# Training_Board.net
KiCad netlist of a schematic drawn in EAGLE
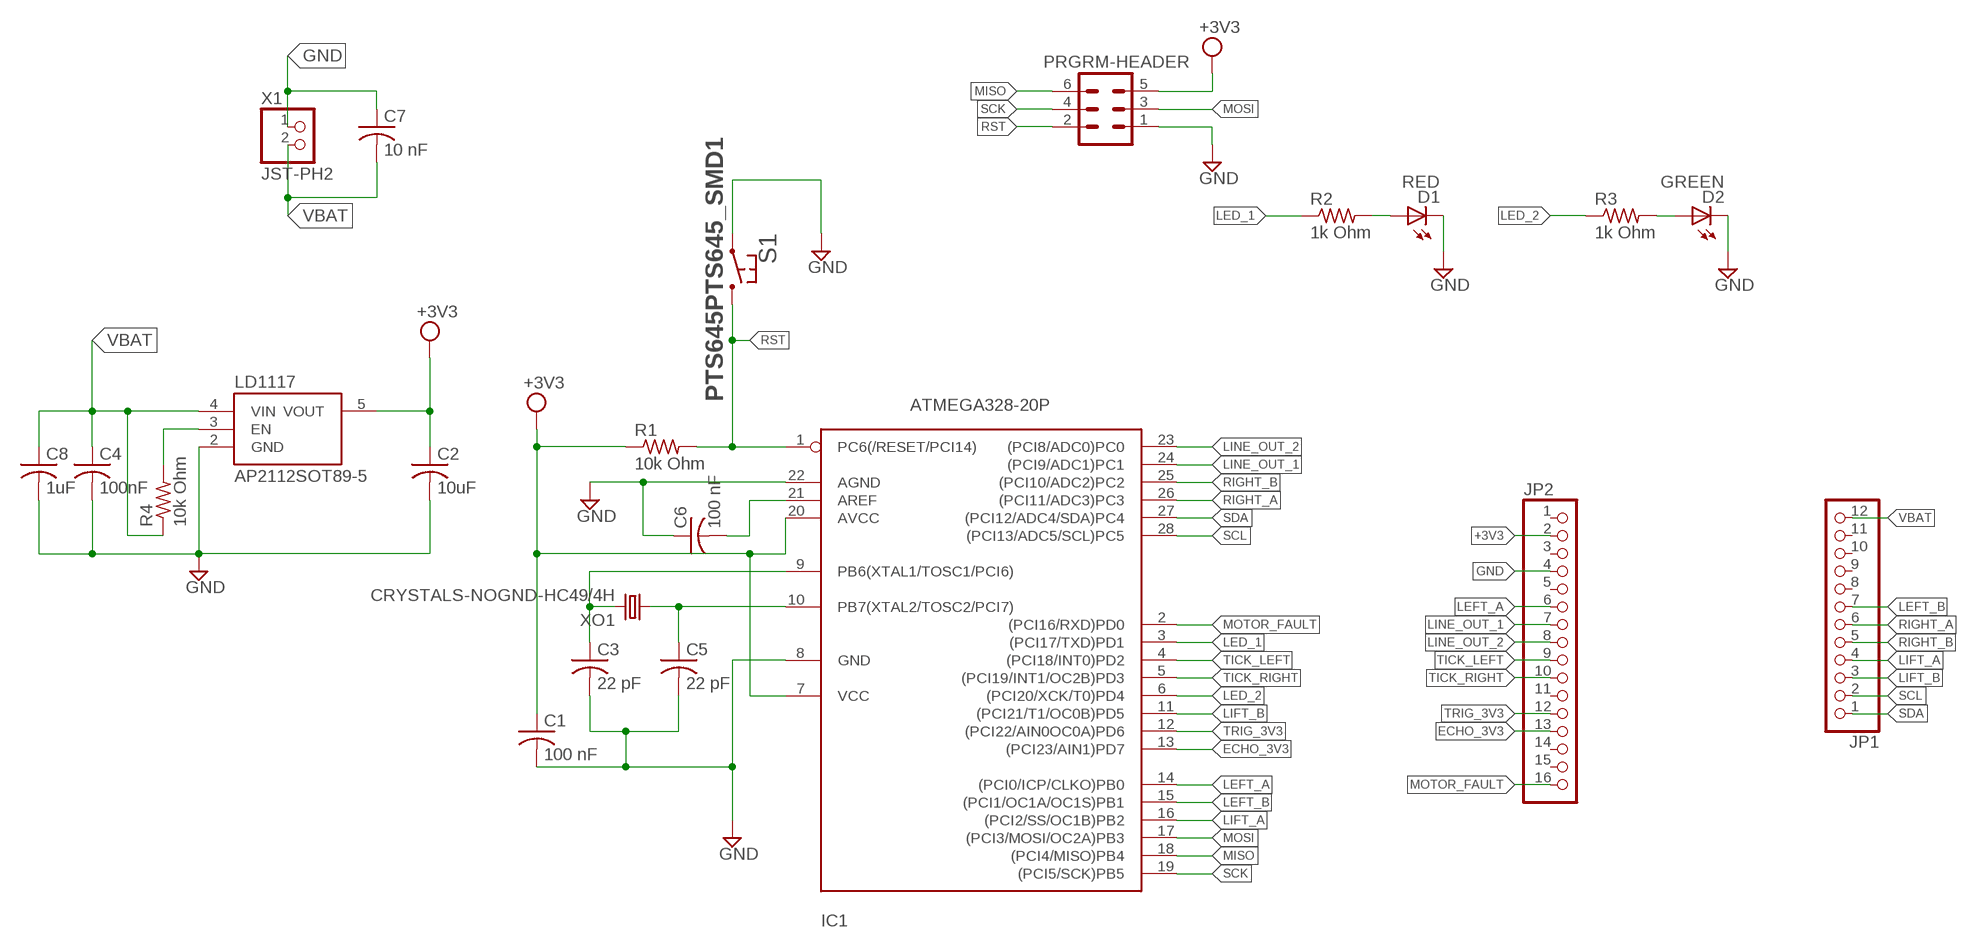
[diagram p0: schematic, sheet 1]

(export (version "E")
  (design (tool "Eeschema 10.0.6"))
  (components
    (comp (ref "C1")
      (value "100 nF")
      (footprint "eagle-import:C0603")
      (libsource (lib "eagle-import") (part "resistor_348_C-USC0603"))
    )
    (comp (ref "C2")
      (value "10uF")
      (footprint "eagle-import:C0603")
      (libsource (lib "eagle-import") (part "C-USC0603"))
    )
    (comp (ref "C3")
      (value "22 pF")
      (footprint "eagle-import:C0603")
      (libsource (lib "eagle-import") (part "resistor_348_C-USC0603"))
    )
    (comp (ref "C4")
      (value "100nF")
      (footprint "eagle-import:C0603")
      (libsource (lib "eagle-import") (part "C-USC0603"))
    )
    (comp (ref "C5")
      (value "22 pF")
      (footprint "eagle-import:C0603")
      (libsource (lib "eagle-import") (part "resistor_348_C-USC0603"))
    )
    (comp (ref "C6")
      (value "100 nF")
      (footprint "eagle-import:C0603")
      (libsource (lib "eagle-import") (part "resistor_348_C-USC0603"))
    )
    (comp (ref "C7")
      (value "10 nF")
      (footprint "eagle-import:C0603")
      (libsource (lib "eagle-import") (part "resistor_348_C-USC0603"))
    )
    (comp (ref "C8")
      (value "1uF")
      (footprint "eagle-import:C0603")
      (libsource (lib "eagle-import") (part "C-USC0603"))
    )
    (comp (ref "D1")
      (value "RED")
      (footprint "eagle-import:CHIP-LED0603")
      (libsource (lib "eagle-import") (part "LEDCHIP-LED0603"))
    )
    (comp (ref "D2")
      (value "GREEN")
      (footprint "eagle-import:CHIP-LED0603")
      (libsource (lib "eagle-import") (part "LEDCHIP-LED0603"))
    )
    (comp (ref "IC1")
      (value "ATMEGA328-20P")
      (footprint "eagle-import:DIL28-3")
      (libsource (lib "eagle-import") (part "ATMEGA328P-20"))
    )
    (comp (ref "JP1")
      (value "PINHD-1X12")
      (footprint "eagle-import:1X12")
      (libsource (lib "eagle-import") (part "PINHD-1X12"))
    )
    (comp (ref "JP2")
      (value "PINHD-1X16")
      (footprint "eagle-import:1X16")
      (libsource (lib "eagle-import") (part "PINHD-1X16"))
    )
    (comp (ref "LD1117")
      (value "AP2112SOT89-5")
      (footprint "eagle-import:SOT95P285X110-5")
      (libsource (lib "eagle-import") (part "AP2112SOT89-5"))
    )
    (comp (ref "PRGRM-HEADER")
      (value "MA03-2")
      (footprint "eagle-import:MA03-2")
      (libsource (lib "eagle-import") (part "MA03-2"))
    )
    (comp (ref "R1")
      (value "10k Ohm")
      (footprint "eagle-import:R0603")
      (libsource (lib "eagle-import") (part "resistor_348_R-US_R0603"))
    )
    (comp (ref "R2")
      (value "1k Ohm")
      (footprint "eagle-import:M0805")
      (libsource (lib "eagle-import") (part "R-US_M0805"))
    )
    (comp (ref "R3")
      (value "1k Ohm")
      (footprint "eagle-import:M0805")
      (libsource (lib "eagle-import") (part "R-US_M0805"))
    )
    (comp (ref "R4")
      (value "10k Ohm")
      (footprint "eagle-import:M0805")
      (libsource (lib "eagle-import") (part "R-US_M0805"))
    )
    (comp (ref "S1")
      (value "PTS645PTS645_SMD1")
      (footprint "eagle-import:PTS645_SMD")
      (libsource (lib "eagle-import") (part "PTS645PTS645_SMD1"))
    )
    (comp (ref "X1")
      (value "JST-PH2")
      (footprint "eagle-import:JST-PH")
      (libsource (lib "eagle-import") (part "JST-PH2"))
    )
    (comp (ref "XO1")
      (value "CRYSTALS-NOGND-HC49/4H")
      (footprint "eagle-import:HC49")
      (libsource (lib "eagle-import") (part "CRYSTALS-NOGND-HC49/4H"))
    )
  )
  (nets
    (net (code "1") (name "+3V3") (class "Default")
      (node (ref "C1") (pin "1") (pinfunction "1_1") (pintype "passive"))
      (node (ref "C2") (pin "1") (pinfunction "1_1") (pintype "passive"))
      (node (ref "IC1") (pin "20") (pinfunction "AVCC_20") (pintype "bidirectional"))
      (node (ref "IC1") (pin "7") (pinfunction "VCC_7") (pintype "bidirectional"))
      (node (ref "JP2") (pin "2") (pinfunction "2_2") (pintype "passive"))
      (node (ref "LD1117") (pin "5") (pinfunction "VOUT_5") (pintype "bidirectional"))
      (node (ref "PRGRM-HEADER") (pin "5") (pinfunction "5_5") (pintype "passive"))
      (node (ref "R1") (pin "1") (pinfunction "1_1") (pintype "passive"))
    )
    (net (code "2") (name "ECHO_3V3") (class "Default")
      (node (ref "IC1") (pin "13") (pinfunction "(PCI23/AIN1)PD7_13") (pintype "bidirectional"))
      (node (ref "JP2") (pin "13") (pinfunction "13_13") (pintype "passive"))
    )
    (net (code "3") (name "GND") (class "Default")
      (node (ref "C1") (pin "2") (pinfunction "2_2") (pintype "passive"))
      (node (ref "C2") (pin "2") (pinfunction "2_2") (pintype "passive"))
      (node (ref "C3") (pin "2") (pinfunction "2_2") (pintype "passive"))
      (node (ref "C4") (pin "2") (pinfunction "2_2") (pintype "passive"))
      (node (ref "C5") (pin "2") (pinfunction "2_2") (pintype "passive"))
      (node (ref "C6") (pin "1") (pinfunction "1_1") (pintype "passive"))
      (node (ref "C7") (pin "1") (pinfunction "1_1") (pintype "passive"))
      (node (ref "C8") (pin "2") (pinfunction "2_2") (pintype "passive"))
      (node (ref "D1") (pin "C") (pinfunction "C_C") (pintype "passive"))
      (node (ref "D2") (pin "C") (pinfunction "C_C") (pintype "passive"))
      (node (ref "IC1") (pin "22") (pinfunction "AGND_22") (pintype "bidirectional"))
      (node (ref "IC1") (pin "8") (pinfunction "GND_8") (pintype "bidirectional"))
      (node (ref "JP2") (pin "4") (pinfunction "4_4") (pintype "passive"))
      (node (ref "LD1117") (pin "2") (pinfunction "GND_2") (pintype "bidirectional"))
      (node (ref "PRGRM-HEADER") (pin "1") (pinfunction "1_1") (pintype "passive"))
      (node (ref "S1") (pin "P$1") (pinfunction "1_P$1") (pintype "passive"))
      (node (ref "S1") (pin "P$2") (pinfunction "1_P$2") (pintype "passive"))
      (node (ref "X1") (pin "1") (pinfunction "1_1") (pintype "passive"))
    )
    (net (code "4") (name "LED_1") (class "Default")
      (node (ref "IC1") (pin "3") (pinfunction "(PCI17/TXD)PD1_3") (pintype "bidirectional"))
      (node (ref "R2") (pin "1") (pinfunction "1_1") (pintype "passive"))
    )
    (net (code "5") (name "LED_2") (class "Default")
      (node (ref "IC1") (pin "6") (pinfunction "(PCI20/XCK/T0)PD4_6") (pintype "bidirectional"))
      (node (ref "R3") (pin "1") (pinfunction "1_1") (pintype "passive"))
    )
    (net (code "6") (name "LEFT_A") (class "Default")
      (node (ref "IC1") (pin "14") (pinfunction "(PCI0/ICP/CLKO)PB0_14") (pintype "bidirectional"))
      (node (ref "JP2") (pin "6") (pinfunction "6_6") (pintype "passive"))
    )
    (net (code "7") (name "LEFT_B") (class "Default")
      (node (ref "IC1") (pin "15") (pinfunction "(PCI1/OC1A/OC1S)PB1_15") (pintype "bidirectional"))
      (node (ref "JP1") (pin "7") (pinfunction "7_7") (pintype "passive"))
    )
    (net (code "8") (name "LIFT_A") (class "Default")
      (node (ref "IC1") (pin "16") (pinfunction "(PCI2/SS/OC1B)PB2_16") (pintype "bidirectional"))
      (node (ref "JP1") (pin "4") (pinfunction "4_4") (pintype "passive"))
    )
    (net (code "9") (name "LIFT_B") (class "Default")
      (node (ref "IC1") (pin "11") (pinfunction "(PCI21/T1/OC0B)PD5_11") (pintype "bidirectional"))
      (node (ref "JP1") (pin "3") (pinfunction "3_3") (pintype "passive"))
    )
    (net (code "10") (name "LINE_OUT_1") (class "Default")
      (node (ref "IC1") (pin "24") (pinfunction "(PCI9/ADC1)PC1_24") (pintype "bidirectional"))
      (node (ref "JP2") (pin "7") (pinfunction "7_7") (pintype "passive"))
    )
    (net (code "11") (name "LINE_OUT_2") (class "Default")
      (node (ref "IC1") (pin "23") (pinfunction "(PCI8/ADC0)PC0_23") (pintype "bidirectional"))
      (node (ref "JP2") (pin "8") (pinfunction "8_8") (pintype "passive"))
    )
    (net (code "12") (name "MISO") (class "Default")
      (node (ref "IC1") (pin "18") (pinfunction "(PCI4/MISO)PB4_18") (pintype "bidirectional"))
      (node (ref "PRGRM-HEADER") (pin "6") (pinfunction "6_6") (pintype "passive"))
    )
    (net (code "13") (name "MOSI") (class "Default")
      (node (ref "IC1") (pin "17") (pinfunction "(PCI3/MOSI/OC2A)PB3_17") (pintype "bidirectional"))
      (node (ref "PRGRM-HEADER") (pin "3") (pinfunction "3_3") (pintype "passive"))
    )
    (net (code "14") (name "MOTOR_FAULT") (class "Default")
      (node (ref "IC1") (pin "2") (pinfunction "(PCI16/RXD)PD0_2") (pintype "bidirectional"))
      (node (ref "JP2") (pin "16") (pinfunction "16_16") (pintype "passive"))
    )
    (net (code "15") (name "Net-(D1-PadA)") (class "Default")
      (node (ref "D1") (pin "A") (pinfunction "A_A") (pintype "passive"))
      (node (ref "R2") (pin "2") (pinfunction "2_2") (pintype "passive"))
    )
    (net (code "16") (name "Net-(D2-PadA)") (class "Default")
      (node (ref "D2") (pin "A") (pinfunction "A_A") (pintype "passive"))
      (node (ref "R3") (pin "2") (pinfunction "2_2") (pintype "passive"))
    )
    (net (code "17") (name "Net-(IC1-AREF)") (class "Default")
      (node (ref "C6") (pin "2") (pinfunction "2_2") (pintype "passive"))
      (node (ref "IC1") (pin "21") (pinfunction "AREF_21") (pintype "bidirectional"))
    )
    (net (code "18") (name "Net-(IC1-PB6(XTAL1{slash}TOSC1{slash}PCI6))") (class "Default")
      (node (ref "C3") (pin "1") (pinfunction "1_1") (pintype "passive"))
      (node (ref "IC1") (pin "9") (pinfunction "PB6(XTAL1/TOSC1/PCI6)_9") (pintype "bidirectional"))
      (node (ref "XO1") (pin "2") (pinfunction "2_2") (pintype "passive"))
    )
    (net (code "19") (name "Net-(IC1-PB7(XTAL2{slash}TOSC2{slash}PCI7))") (class "Default")
      (node (ref "C5") (pin "1") (pinfunction "1_1") (pintype "passive"))
      (node (ref "IC1") (pin "10") (pinfunction "PB7(XTAL2/TOSC2/PCI7)_10") (pintype "bidirectional"))
      (node (ref "XO1") (pin "1") (pinfunction "1_1") (pintype "passive"))
    )
    (net (code "20") (name "Net-(LD1117-EN)") (class "Default")
      (node (ref "LD1117") (pin "3") (pinfunction "EN_3") (pintype "bidirectional"))
      (node (ref "R4") (pin "2") (pinfunction "2_2") (pintype "passive"))
    )
    (net (code "21") (name "RIGHT_A") (class "Default")
      (node (ref "IC1") (pin "26") (pinfunction "(PCI11/ADC3)PC3_26") (pintype "bidirectional"))
      (node (ref "JP1") (pin "6") (pinfunction "6_6") (pintype "passive"))
    )
    (net (code "22") (name "RIGHT_B") (class "Default")
      (node (ref "IC1") (pin "25") (pinfunction "(PCI10/ADC2)PC2_25") (pintype "bidirectional"))
      (node (ref "JP1") (pin "5") (pinfunction "5_5") (pintype "passive"))
    )
    (net (code "23") (name "RST") (class "Default")
      (node (ref "IC1") (pin "1") (pinfunction "PC6(/RESET/PCI14)_1") (pintype "bidirectional"))
      (node (ref "PRGRM-HEADER") (pin "2") (pinfunction "2_2") (pintype "passive"))
      (node (ref "R1") (pin "2") (pinfunction "2_2") (pintype "passive"))
      (node (ref "S1") (pin "P$3") (pinfunction "2_P$3") (pintype "passive"))
      (node (ref "S1") (pin "P$4") (pinfunction "2_P$4") (pintype "passive"))
    )
    (net (code "24") (name "SCK") (class "Default")
      (node (ref "IC1") (pin "19") (pinfunction "(PCI5/SCK)PB5_19") (pintype "bidirectional"))
      (node (ref "PRGRM-HEADER") (pin "4") (pinfunction "4_4") (pintype "passive"))
    )
    (net (code "25") (name "SCL") (class "Default")
      (node (ref "IC1") (pin "28") (pinfunction "(PCI13/ADC5/SCL)PC5_28") (pintype "bidirectional"))
      (node (ref "JP1") (pin "2") (pinfunction "2_2") (pintype "passive"))
    )
    (net (code "26") (name "SDA") (class "Default")
      (node (ref "IC1") (pin "27") (pinfunction "(PCI12/ADC4/SDA)PC4_27") (pintype "bidirectional"))
      (node (ref "JP1") (pin "1") (pinfunction "1_1") (pintype "passive"))
    )
    (net (code "27") (name "TICK_LEFT") (class "Default")
      (node (ref "IC1") (pin "4") (pinfunction "(PCI18/INT0)PD2_4") (pintype "bidirectional"))
      (node (ref "JP2") (pin "9") (pinfunction "9_9") (pintype "passive"))
    )
    (net (code "28") (name "TICK_RIGHT") (class "Default")
      (node (ref "IC1") (pin "5") (pinfunction "(PCI19/INT1/OC2B)PD3_5") (pintype "bidirectional"))
      (node (ref "JP2") (pin "10") (pinfunction "10_10") (pintype "passive"))
    )
    (net (code "29") (name "TRIG_3V3") (class "Default")
      (node (ref "IC1") (pin "12") (pinfunction "(PCI22/AIN0OC0A)PD6_12") (pintype "bidirectional"))
      (node (ref "JP2") (pin "12") (pinfunction "12_12") (pintype "passive"))
    )
    (net (code "30") (name "VBAT") (class "Default")
      (node (ref "C4") (pin "1") (pinfunction "1_1") (pintype "passive"))
      (node (ref "C7") (pin "2") (pinfunction "2_2") (pintype "passive"))
      (node (ref "C8") (pin "1") (pinfunction "1_1") (pintype "passive"))
      (node (ref "JP1") (pin "12") (pinfunction "12_12") (pintype "passive"))
      (node (ref "LD1117") (pin "4") (pinfunction "VIN_4") (pintype "bidirectional"))
      (node (ref "R4") (pin "1") (pinfunction "1_1") (pintype "passive"))
      (node (ref "X1") (pin "2") (pinfunction "2_2") (pintype "passive"))
    )
    (net (code "31") (name "unconnected-(JP1-Pad8)") (class "Default")
      (node (ref "JP1") (pin "8") (pinfunction "8_8") (pintype "passive"))
    )
    (net (code "32") (name "unconnected-(JP1-Pad9)") (class "Default")
      (node (ref "JP1") (pin "9") (pinfunction "9_9") (pintype "passive"))
    )
    (net (code "33") (name "unconnected-(JP1-Pad10)") (class "Default")
      (node (ref "JP1") (pin "10") (pinfunction "10_10") (pintype "passive"))
    )
    (net (code "34") (name "unconnected-(JP1-Pad11)") (class "Default")
      (node (ref "JP1") (pin "11") (pinfunction "11_11") (pintype "passive"))
    )
    (net (code "35") (name "unconnected-(JP2-Pad1)") (class "Default")
      (node (ref "JP2") (pin "1") (pinfunction "1_1") (pintype "passive"))
    )
    (net (code "36") (name "unconnected-(JP2-Pad3)") (class "Default")
      (node (ref "JP2") (pin "3") (pinfunction "3_3") (pintype "passive"))
    )
    (net (code "37") (name "unconnected-(JP2-Pad5)") (class "Default")
      (node (ref "JP2") (pin "5") (pinfunction "5_5") (pintype "passive"))
    )
    (net (code "38") (name "unconnected-(JP2-Pad11)") (class "Default")
      (node (ref "JP2") (pin "11") (pinfunction "11_11") (pintype "passive"))
    )
    (net (code "39") (name "unconnected-(JP2-Pad14)") (class "Default")
      (node (ref "JP2") (pin "14") (pinfunction "14_14") (pintype "passive"))
    )
    (net (code "40") (name "unconnected-(JP2-Pad15)") (class "Default")
      (node (ref "JP2") (pin "15") (pinfunction "15_15") (pintype "passive"))
    )
  )
)
